# bpf-UHF-BPF-C450.net
KiCad netlist of a schematic drawn in EAGLE
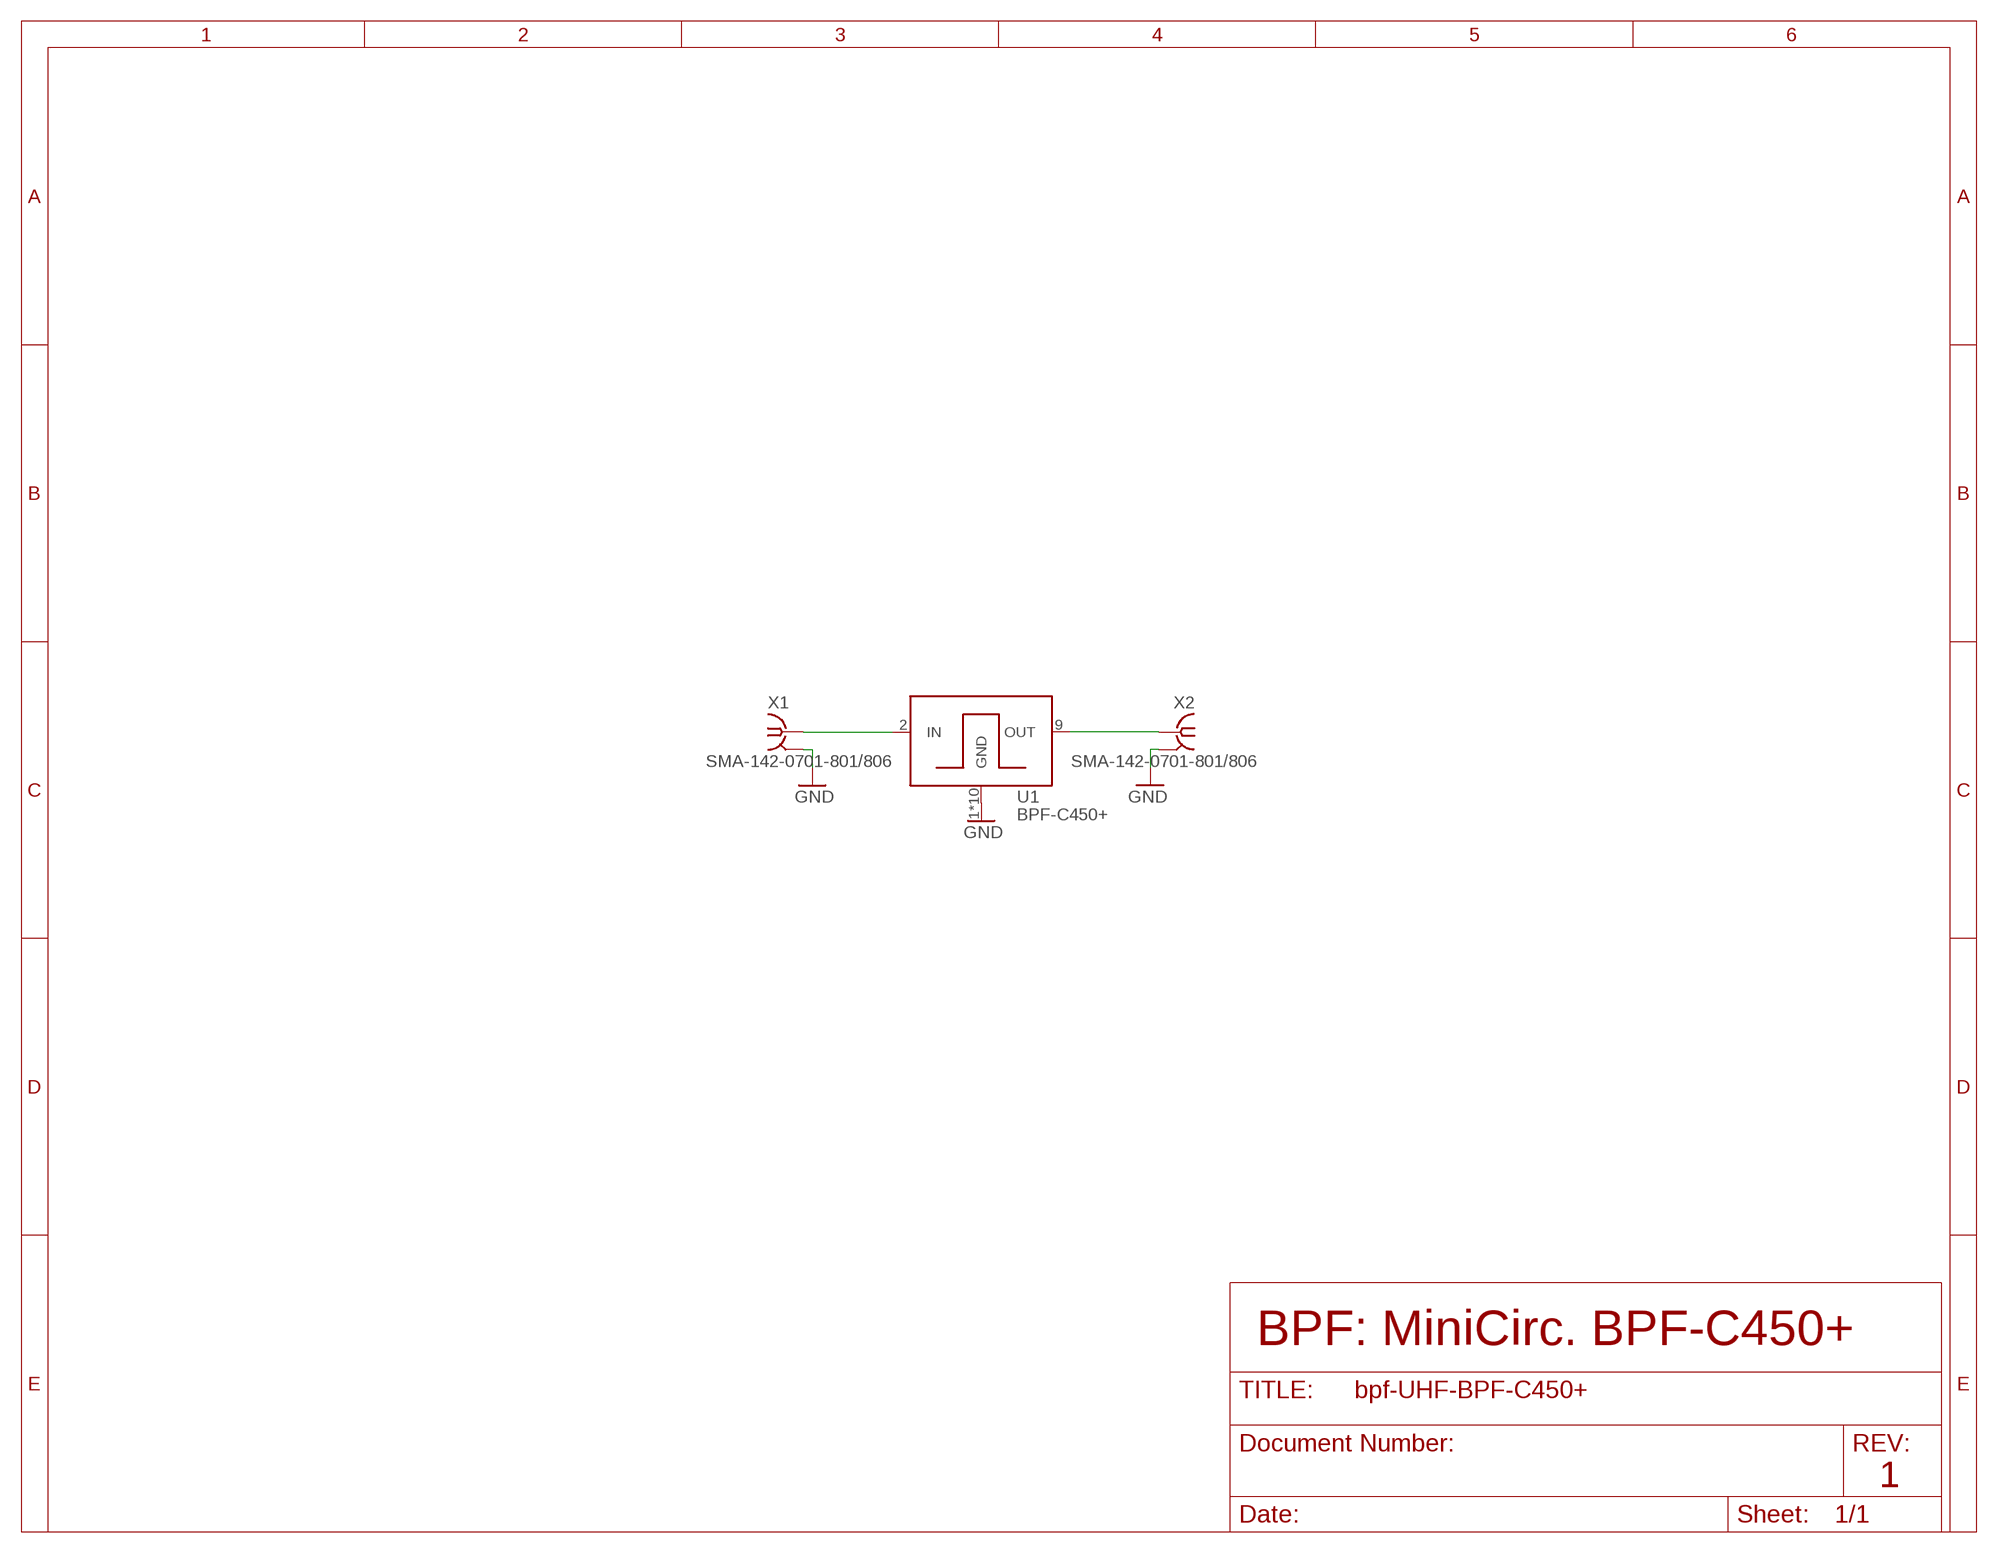
[diagram p0: schematic, sheet 1]

(export (version "E")
  (design (tool "Eeschema 10.0.6"))
  (components
    (comp (ref "U1")
      (value "BPF-C450+")
      (footprint "eagle-import:BPF-C450+")
      (libsource (lib "eagle-import") (part "BPF-C450+"))
    )
    (comp (ref "X1")
      (value "SMA-142-0701-801/806")
      (footprint "eagle-import:J502-ND-142-0701-801_806")
      (fields (field (name "MF") "JOHNSON COMPONENTS") (field (name "MPN") "142-0701-801"))
      (libsource (lib "eagle-import") (part "SMA-142-0701-801/806"))
    )
    (comp (ref "X2")
      (value "SMA-142-0701-801/806")
      (footprint "eagle-import:J502-ND-142-0701-801_806")
      (fields (field (name "MF") "JOHNSON COMPONENTS") (field (name "MPN") "142-0701-801"))
      (libsource (lib "eagle-import") (part "SMA-142-0701-801/806"))
    )
  )
  (nets
    (net (code "1") (name "GND") (class "Default")
      (node (ref "U1") (pin "1") (pinfunction "GND_1") (pintype "power_in"))
      (node (ref "U1") (pin "10") (pinfunction "GND_10") (pintype "power_in"))
      (node (ref "U1") (pin "11") (pinfunction "GND_11") (pintype "power_in"))
      (node (ref "U1") (pin "12") (pinfunction "GND_12") (pintype "power_in"))
      (node (ref "U1") (pin "14") (pinfunction "GND_14") (pintype "power_in"))
      (node (ref "U1") (pin "3") (pinfunction "GND_3") (pintype "power_in"))
      (node (ref "U1") (pin "4") (pinfunction "GND_4") (pintype "power_in"))
      (node (ref "U1") (pin "5") (pinfunction "GND_5") (pintype "power_in"))
      (node (ref "U1") (pin "7") (pinfunction "GND_7") (pintype "power_in"))
      (node (ref "U1") (pin "8") (pinfunction "GND_8") (pintype "power_in"))
      (node (ref "X1") (pin "G@1") (pinfunction "2_G@1") (pintype "passive"))
      (node (ref "X1") (pin "G@2") (pinfunction "2_G@2") (pintype "passive"))
      (node (ref "X1") (pin "G@3") (pinfunction "2_G@3") (pintype "passive"))
      (node (ref "X1") (pin "G@4") (pinfunction "2_G@4") (pintype "passive"))
      (node (ref "X2") (pin "G@1") (pinfunction "2_G@1") (pintype "passive"))
      (node (ref "X2") (pin "G@2") (pinfunction "2_G@2") (pintype "passive"))
      (node (ref "X2") (pin "G@3") (pinfunction "2_G@3") (pintype "passive"))
      (node (ref "X2") (pin "G@4") (pinfunction "2_G@4") (pintype "passive"))
    )
    (net (code "2") (name "Net-(U1-IN)") (class "Default")
      (node (ref "U1") (pin "2") (pinfunction "IN_2") (pintype "input"))
      (node (ref "X1") (pin "1") (pinfunction "1_1") (pintype "passive"))
    )
    (net (code "3") (name "Net-(U1-OUT)") (class "Default")
      (node (ref "U1") (pin "9") (pinfunction "OUT_9") (pintype "output"))
      (node (ref "X2") (pin "1") (pinfunction "1_1") (pintype "passive"))
    )
  )
)
